# Interface_BUS.net
KiCad netlist of a schematic drawn in Altium Designer
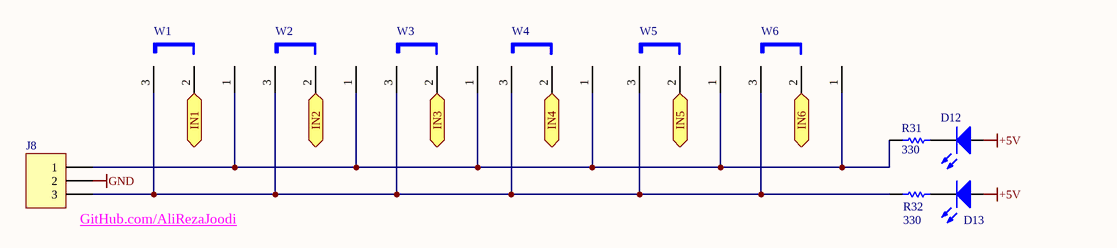
[diagram p0: Interface_BUS.SchDoc]

(export (version "E")
  (design (tool "Eeschema 10.0.6"))
  (components
    (comp (ref "D12")
      (value "LED")
      (footprint "LED-5mm_Red")
      (description "Typical INFRARED GaAs LED")
      (fields (field (name "MANUFACTURER") "Generic Components") (field (name "PUBLISHER") "Altium Limited"))
      (libsource (lib "Miscellaneous Devices") (part "LED"))
    )
    (comp (ref "D13")
      (value "LED")
      (footprint "LED-5mm_Red")
      (description "Typical INFRARED GaAs LED")
      (fields (field (name "MANUFACTURER") "Generic Components") (field (name "PUBLISHER") "Altium Limited"))
      (libsource (lib "Miscellaneous Devices") (part "LED"))
    )
    (comp (ref "J8")
      (value "Header 3")
      (footprint "HDR1X3")
      (description "Header, 3-Pin")
      (fields (field (name "MANUFACTURER") "Generic Components") (field (name "PUBLISHER") "Altium Limited"))
      (libsource (lib "Miscellaneous Connectors") (part "Header 3"))
    )
    (comp (ref "R31")
      (value "330")
      (footprint "AXIAL-0.4")
      (description "Resistor")
      (fields (field (name "MANUFACTURER") "Generic Components") (field (name "PUBLISHER") "Altium Limited"))
      (libsource (lib "Miscellaneous Devices") (part "Res1"))
    )
    (comp (ref "R32")
      (value "330")
      (footprint "AXIAL-0.4")
      (description "Resistor")
      (fields (field (name "MANUFACTURER") "Generic Components") (field (name "PUBLISHER") "Altium Limited"))
      (libsource (lib "Miscellaneous Devices") (part "Res1"))
    )
    (comp (ref "W1")
      (value "Jumper 3pin")
      (footprint "SIP3")
      (description "Jumper Wire")
      (fields (field (name "MANUFACTURER") "Generic Components") (field (name "PUBLISHER") "Altium Limited"))
      (libsource (lib "my Libraries") (part "Jumper 3pin"))
    )
    (comp (ref "W2")
      (value "Jumper 3pin")
      (footprint "SIP3")
      (description "Jumper Wire")
      (fields (field (name "MANUFACTURER") "Generic Components") (field (name "PUBLISHER") "Altium Limited"))
      (libsource (lib "my Libraries") (part "Jumper 3pin"))
    )
    (comp (ref "W3")
      (value "Jumper 3pin")
      (footprint "SIP3")
      (description "Jumper Wire")
      (fields (field (name "MANUFACTURER") "Generic Components") (field (name "PUBLISHER") "Altium Limited"))
      (libsource (lib "my Libraries") (part "Jumper 3pin"))
    )
    (comp (ref "W4")
      (value "Jumper 3pin")
      (footprint "SIP3")
      (description "Jumper Wire")
      (fields (field (name "MANUFACTURER") "Generic Components") (field (name "PUBLISHER") "Altium Limited"))
      (libsource (lib "my Libraries") (part "Jumper 3pin"))
    )
    (comp (ref "W5")
      (value "Jumper 3pin")
      (footprint "SIP3")
      (description "Jumper Wire")
      (fields (field (name "MANUFACTURER") "Generic Components") (field (name "PUBLISHER") "Altium Limited"))
      (libsource (lib "my Libraries") (part "Jumper 3pin"))
    )
    (comp (ref "W6")
      (value "Jumper 3pin")
      (footprint "SIP3")
      (description "Jumper Wire")
      (fields (field (name "MANUFACTURER") "Generic Components") (field (name "PUBLISHER") "Altium Limited"))
      (libsource (lib "my Libraries") (part "Jumper 3pin"))
    )
  )
  (nets
    (net (code "1") (name "+5V") (class "Default")
      (node (ref "D12") (pin "1") (pinfunction "A_1") (pintype "passive"))
      (node (ref "D13") (pin "1") (pinfunction "A_1") (pintype "passive"))
    )
    (net (code "2") (name "/IN1") (class "Default")
      (node (ref "W1") (pin "2") (pinfunction "2_2") (pintype "passive"))
    )
    (net (code "3") (name "/IN2") (class "Default")
      (node (ref "W2") (pin "2") (pinfunction "2_2") (pintype "passive"))
    )
    (net (code "4") (name "/IN3") (class "Default")
      (node (ref "W3") (pin "2") (pinfunction "2_2") (pintype "passive"))
    )
    (net (code "5") (name "/IN4") (class "Default")
      (node (ref "W4") (pin "2") (pinfunction "2_2") (pintype "passive"))
    )
    (net (code "6") (name "/IN5") (class "Default")
      (node (ref "W5") (pin "2") (pinfunction "2_2") (pintype "passive"))
    )
    (net (code "7") (name "/IN6") (class "Default")
      (node (ref "W6") (pin "2") (pinfunction "2_2") (pintype "passive"))
    )
    (net (code "8") (name "GND") (class "Default")
      (node (ref "J8") (pin "2") (pinfunction "2_2") (pintype "passive"))
    )
    (net (code "9") (name "Net-(D12-K)") (class "Default")
      (node (ref "D12") (pin "2") (pinfunction "K_2") (pintype "passive"))
      (node (ref "R31") (pin "1") (pinfunction "1_1") (pintype "passive"))
    )
    (net (code "10") (name "Net-(D13-K)") (class "Default")
      (node (ref "D13") (pin "2") (pinfunction "K_2") (pintype "passive"))
      (node (ref "R32") (pin "1") (pinfunction "1_1") (pintype "passive"))
    )
    (net (code "11") (name "Net-(J8-Pad1)") (class "Default")
      (node (ref "J8") (pin "1") (pinfunction "1_1") (pintype "passive"))
      (node (ref "R31") (pin "2") (pinfunction "2_2") (pintype "passive"))
      (node (ref "W1") (pin "1") (pinfunction "1_1") (pintype "passive"))
      (node (ref "W2") (pin "1") (pinfunction "1_1") (pintype "passive"))
      (node (ref "W3") (pin "1") (pinfunction "1_1") (pintype "passive"))
      (node (ref "W4") (pin "1") (pinfunction "1_1") (pintype "passive"))
      (node (ref "W5") (pin "1") (pinfunction "1_1") (pintype "passive"))
      (node (ref "W6") (pin "1") (pinfunction "1_1") (pintype "passive"))
    )
    (net (code "12") (name "Net-(J8-Pad3)") (class "Default")
      (node (ref "J8") (pin "3") (pinfunction "3_3") (pintype "passive"))
      (node (ref "R32") (pin "2") (pinfunction "2_2") (pintype "passive"))
      (node (ref "W1") (pin "3") (pinfunction "3_3") (pintype "passive"))
      (node (ref "W2") (pin "3") (pinfunction "3_3") (pintype "passive"))
      (node (ref "W3") (pin "3") (pinfunction "3_3") (pintype "passive"))
      (node (ref "W4") (pin "3") (pinfunction "3_3") (pintype "passive"))
      (node (ref "W5") (pin "3") (pinfunction "3_3") (pintype "passive"))
      (node (ref "W6") (pin "3") (pinfunction "3_3") (pintype "passive"))
    )
  )
)
